# Connectors.net
KiCad netlist of a schematic drawn in Altium Designer
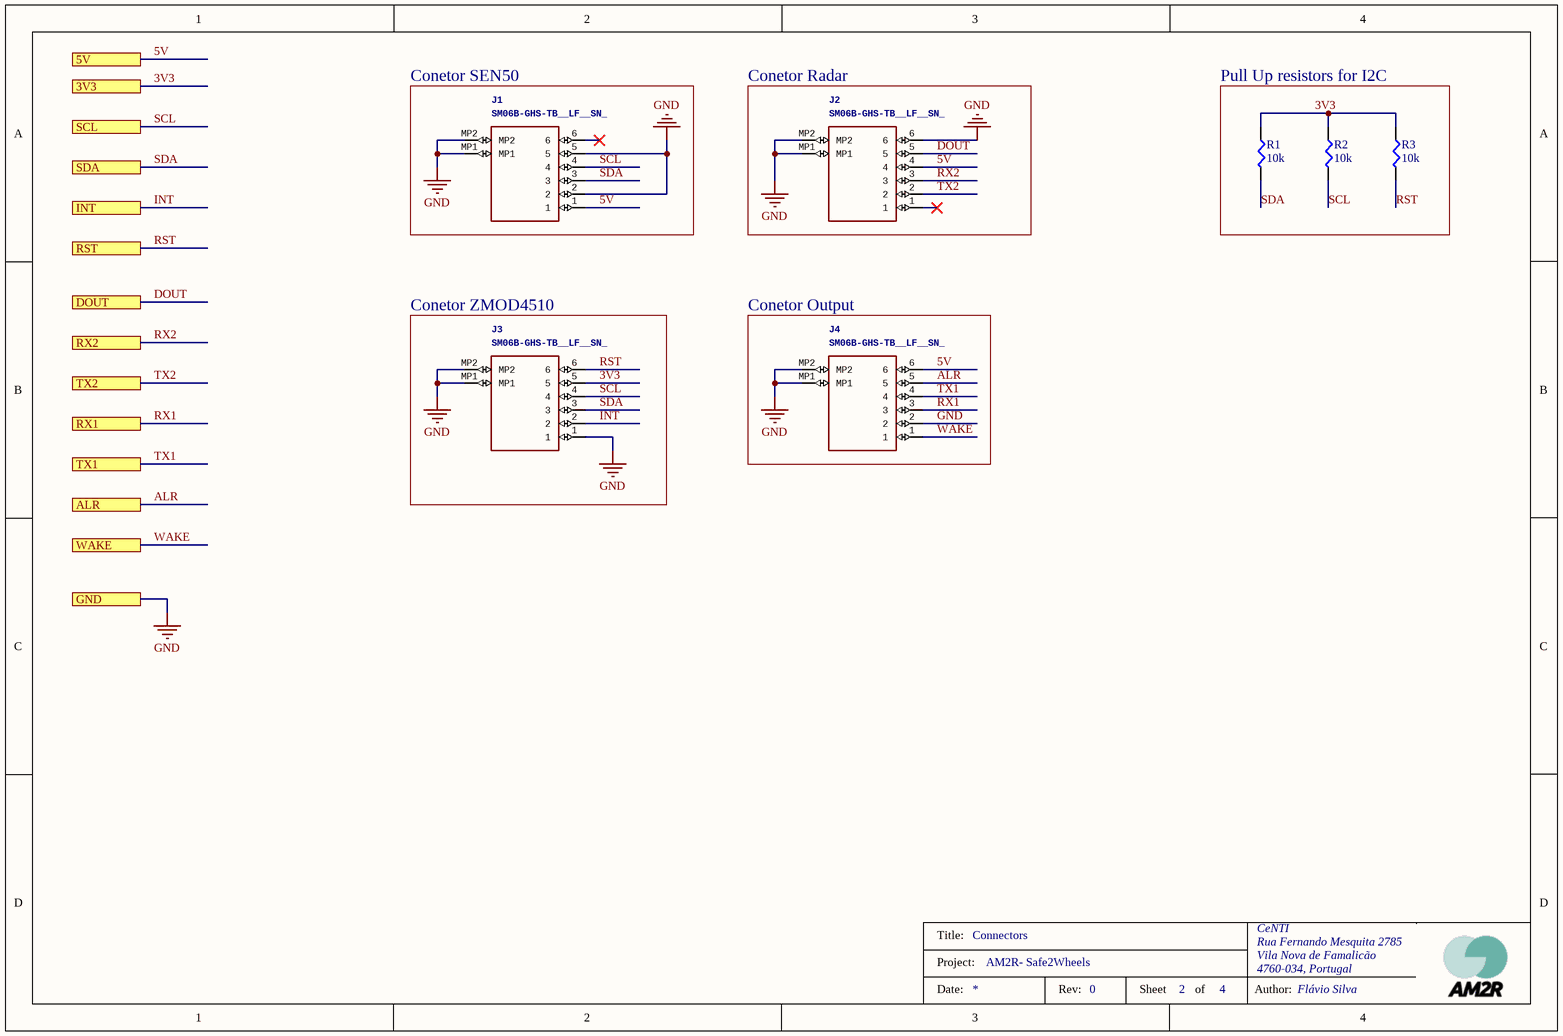
[diagram p0: Connectors.SchDoc]

(export (version "E")
  (design (tool "Eeschema 10.0.6"))
  (components
    (comp (ref "J1")
      (value "SM06B-GHS-TB__LF__SN_")
      (footprint "SM06BGHSTBLFSN")
      (description "Conn Shrouded Header HDR 6 POS 1.25mm Solder RA Side Entry SMD T/R   Source:  Datasheet")
      (fields (field (name "MANUFACTURER_PART_NUMBER") "SM06B-GHS-TB (LF)(SN)"))
      (libsource (lib "FDS") (part "SM06B-GHS-TB__LF__SN_"))
    )
    (comp (ref "J2")
      (value "SM06B-GHS-TB__LF__SN_")
      (footprint "SM06BGHSTBLFSN")
      (description "Conn Shrouded Header HDR 6 POS 1.25mm Solder RA Side Entry SMD T/R   Source:  Datasheet")
      (fields (field (name "MANUFACTURER_PART_NUMBER") "SM06B-GHS-TB (LF)(SN)"))
      (libsource (lib "FDS") (part "SM06B-GHS-TB__LF__SN_"))
    )
    (comp (ref "J3")
      (value "SM06B-GHS-TB__LF__SN_")
      (footprint "SM06BGHSTBLFSN")
      (description "Conn Shrouded Header HDR 6 POS 1.25mm Solder RA Side Entry SMD T/R   Source:  Datasheet")
      (fields (field (name "MANUFACTURER_PART_NUMBER") "SM06B-GHS-TB (LF)(SN)"))
      (libsource (lib "FDS") (part "SM06B-GHS-TB__LF__SN_"))
    )
    (comp (ref "J4")
      (value "SM06B-GHS-TB__LF__SN_")
      (footprint "SM06BGHSTBLFSN")
      (description "Conn Shrouded Header HDR 6 POS 1.25mm Solder RA Side Entry SMD T/R   Source:  Datasheet")
      (fields (field (name "MANUFACTURER_PART_NUMBER") "SM06B-GHS-TB (LF)(SN)"))
      (libsource (lib "FDS") (part "SM06B-GHS-TB__LF__SN_"))
    )
    (comp (ref "R1")
      (value "10k")
      (footprint "SMD-0402-RES")
      (description "RES SMD 10K OHM 5% 1/10W 0402")
      (fields (field (name "PART NUMBER") "ERJ-2GEJ103X") (field (name "DIGI-KEY PART NUMBER") "P10KJCT-ND"))
      (libsource (lib "Panasonic_ERJ_0402") (part "ERJ-2GEJ103X"))
    )
    (comp (ref "R2")
      (value "10k")
      (footprint "SMD-0402-RES")
      (description "RES SMD 10K OHM 5% 1/10W 0402")
      (fields (field (name "PART NUMBER") "ERJ-2GEJ103X") (field (name "DIGI-KEY PART NUMBER") "P10KJCT-ND"))
      (libsource (lib "Panasonic_ERJ_0402") (part "ERJ-2GEJ103X"))
    )
    (comp (ref "R3")
      (value "10k")
      (footprint "SMD-0402-RES")
      (description "RES SMD 10K OHM 5% 1/10W 0402")
      (fields (field (name "PART NUMBER") "ERJ-2GEJ103X") (field (name "DIGI-KEY PART NUMBER") "P10KJCT-ND"))
      (libsource (lib "Panasonic_ERJ_0402") (part "ERJ-2GEJ103X"))
    )
  )
  (nets
    (net (code "1") (name "/3V3") (class "Default")
      (node (ref "J3") (pin "5") (pinfunction "5_5") (pintype "bidirectional"))
      (node (ref "R1") (pin "1") (pinfunction "1_1") (pintype "passive"))
      (node (ref "R2") (pin "1") (pinfunction "1_1") (pintype "passive"))
      (node (ref "R3") (pin "1") (pinfunction "1_1") (pintype "passive"))
    )
    (net (code "2") (name "/5V") (class "Default")
      (node (ref "J1") (pin "1") (pinfunction "1_1") (pintype "bidirectional"))
      (node (ref "J2") (pin "4") (pinfunction "4_4") (pintype "bidirectional"))
      (node (ref "J4") (pin "6") (pinfunction "6_6") (pintype "bidirectional"))
    )
    (net (code "3") (name "/ALR") (class "Default")
      (node (ref "J4") (pin "5") (pinfunction "5_5") (pintype "bidirectional"))
    )
    (net (code "4") (name "/DOUT") (class "Default")
      (node (ref "J2") (pin "5") (pinfunction "5_5") (pintype "bidirectional"))
    )
    (net (code "5") (name "/INT") (class "Default")
      (node (ref "J3") (pin "2") (pinfunction "2_2") (pintype "bidirectional"))
    )
    (net (code "6") (name "/RST") (class "Default")
      (node (ref "J3") (pin "6") (pinfunction "6_6") (pintype "bidirectional"))
      (node (ref "R3") (pin "2") (pinfunction "2_2") (pintype "passive"))
    )
    (net (code "7") (name "/RX1") (class "Default")
      (node (ref "J4") (pin "3") (pinfunction "3_3") (pintype "bidirectional"))
    )
    (net (code "8") (name "/RX2") (class "Default")
      (node (ref "J2") (pin "3") (pinfunction "3_3") (pintype "bidirectional"))
    )
    (net (code "9") (name "/SCL") (class "Default")
      (node (ref "J1") (pin "4") (pinfunction "4_4") (pintype "bidirectional"))
      (node (ref "J3") (pin "4") (pinfunction "4_4") (pintype "bidirectional"))
      (node (ref "R2") (pin "2") (pinfunction "2_2") (pintype "passive"))
    )
    (net (code "10") (name "/SDA") (class "Default")
      (node (ref "J1") (pin "3") (pinfunction "3_3") (pintype "bidirectional"))
      (node (ref "J3") (pin "3") (pinfunction "3_3") (pintype "bidirectional"))
      (node (ref "R1") (pin "2") (pinfunction "2_2") (pintype "passive"))
    )
    (net (code "11") (name "/TX1") (class "Default")
      (node (ref "J4") (pin "4") (pinfunction "4_4") (pintype "bidirectional"))
    )
    (net (code "12") (name "/TX2") (class "Default")
      (node (ref "J2") (pin "2") (pinfunction "2_2") (pintype "bidirectional"))
    )
    (net (code "13") (name "/WAKE") (class "Default")
      (node (ref "J4") (pin "1") (pinfunction "1_1") (pintype "bidirectional"))
    )
    (net (code "14") (name "GND") (class "Default")
      (node (ref "J1") (pin "2") (pinfunction "2_2") (pintype "bidirectional"))
      (node (ref "J1") (pin "5") (pinfunction "5_5") (pintype "bidirectional"))
      (node (ref "J1") (pin "MP1") (pinfunction "MP1_MP1") (pintype "bidirectional"))
      (node (ref "J1") (pin "MP2") (pinfunction "MP2_MP2") (pintype "bidirectional"))
      (node (ref "J2") (pin "6") (pinfunction "6_6") (pintype "bidirectional"))
      (node (ref "J2") (pin "MP1") (pinfunction "MP1_MP1") (pintype "bidirectional"))
      (node (ref "J2") (pin "MP2") (pinfunction "MP2_MP2") (pintype "bidirectional"))
      (node (ref "J3") (pin "1") (pinfunction "1_1") (pintype "bidirectional"))
      (node (ref "J3") (pin "MP1") (pinfunction "MP1_MP1") (pintype "bidirectional"))
      (node (ref "J3") (pin "MP2") (pinfunction "MP2_MP2") (pintype "bidirectional"))
      (node (ref "J4") (pin "2") (pinfunction "2_2") (pintype "bidirectional"))
      (node (ref "J4") (pin "MP1") (pinfunction "MP1_MP1") (pintype "bidirectional"))
      (node (ref "J4") (pin "MP2") (pinfunction "MP2_MP2") (pintype "bidirectional"))
    )
    (net (code "15") (name "unconnected-(J1-Pad6)") (class "Default")
      (node (ref "J1") (pin "6") (pinfunction "6_6") (pintype "bidirectional+no_connect"))
    )
    (net (code "16") (name "unconnected-(J2-Pad1)") (class "Default")
      (node (ref "J2") (pin "1") (pinfunction "1_1") (pintype "bidirectional+no_connect"))
    )
  )
)
